# LevelShift.net
KiCad netlist of a schematic drawn in Altium Designer
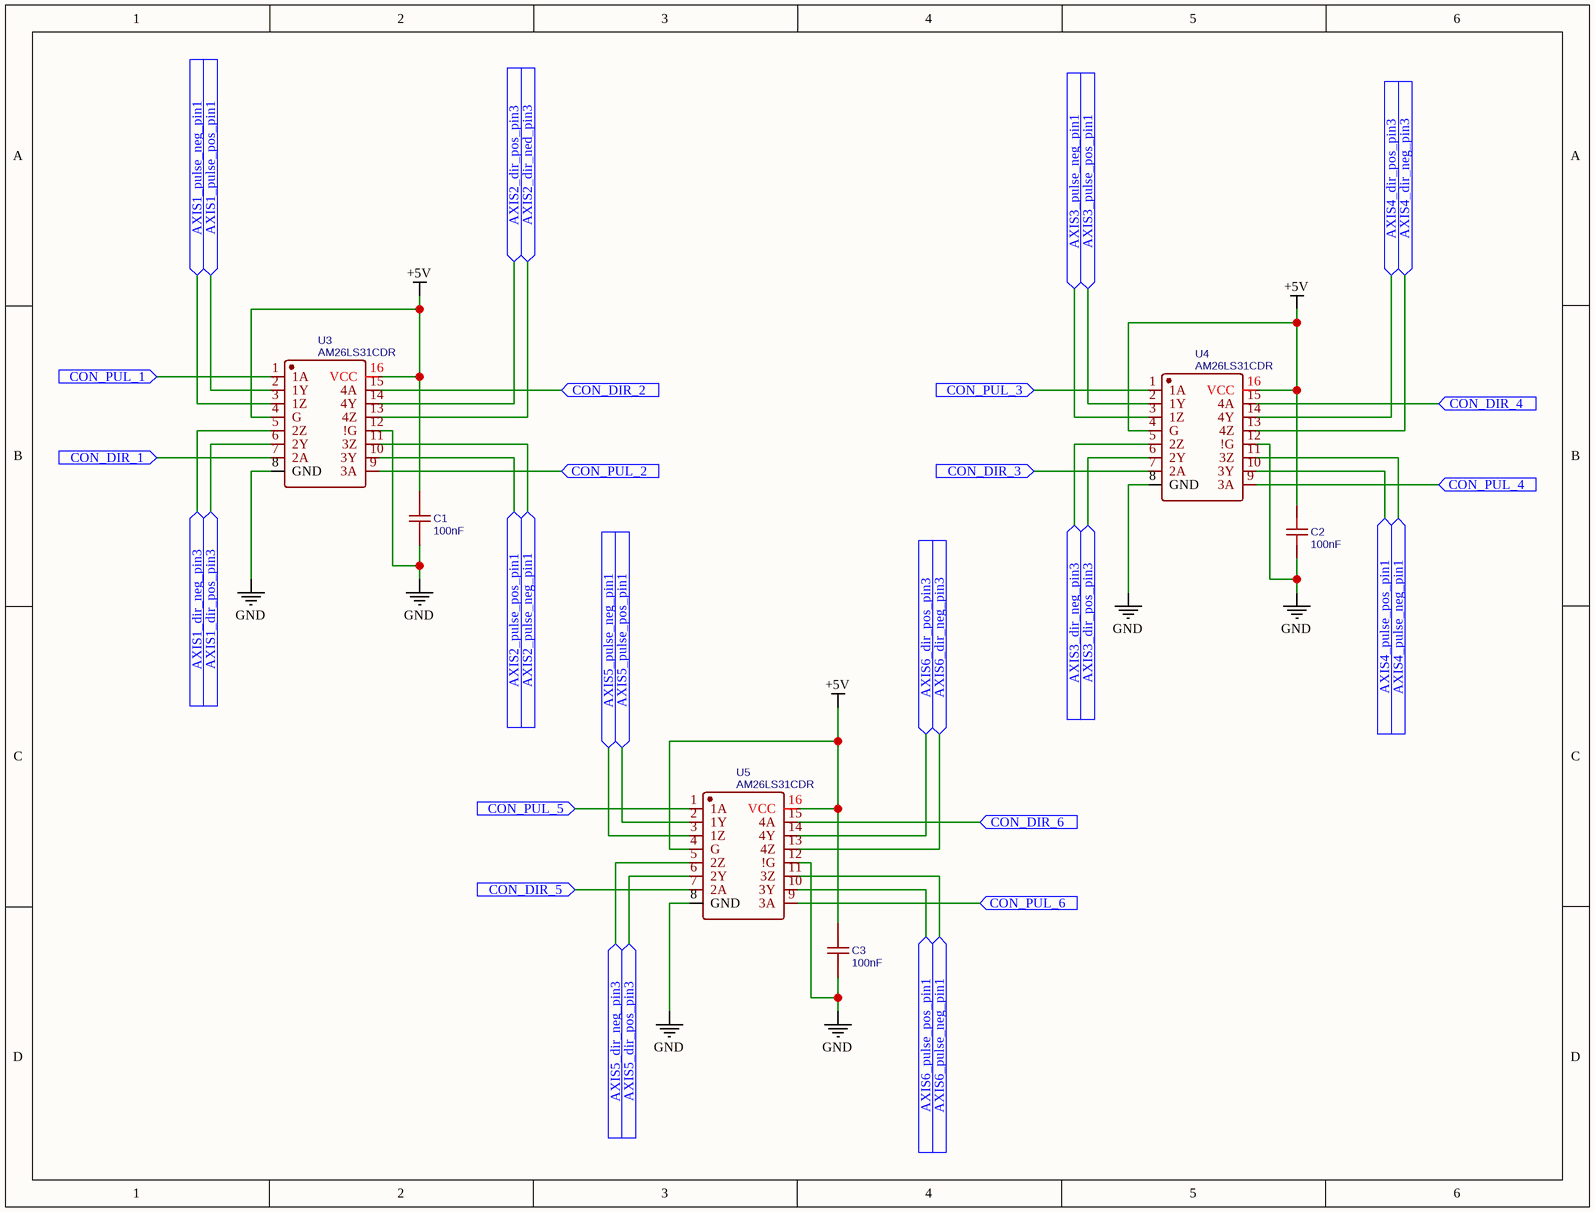
[diagram p0: LevelShift.schdoc]

(export (version "E")
  (design (tool "Eeschema 10.0.6"))
  (components
    (comp (ref "C1")
      (value "100nF")
      (fields
        (field (name "MANUFACTURER") "YAGEO")
        (field (name "MANUFACTURER PART") "CC0805KRX7R8BB104")
        (field (name "CONTRIBUTOR") "LCSC")
      )
      (libsource (lib "altium-import") (part "root_3_100nF_"))
    )
    (comp (ref "C2")
      (value "100nF")
      (fields
        (field (name "MANUFACTURER") "YAGEO")
        (field (name "MANUFACTURER PART") "CC0805KRX7R8BB104")
        (field (name "CONTRIBUTOR") "LCSC")
      )
      (libsource (lib "altium-import") (part "root_3_100nF_"))
    )
    (comp (ref "C3")
      (value "100nF")
      (fields
        (field (name "MANUFACTURER") "YAGEO")
        (field (name "MANUFACTURER PART") "CC0805KRX7R8BB104")
        (field (name "CONTRIBUTOR") "LCSC")
      )
      (libsource (lib "altium-import") (part "root_3_100nF_"))
    )
    (comp (ref "U3")
      (value "AM26LS31CDR")
      (fields (field (name "MANUFACTURER") "TI(德州仪器)"))
      (libsource (lib "altium-import") (part "root_0_AM26LS31CDR_"))
    )
    (comp (ref "U4")
      (value "AM26LS31CDR")
      (fields (field (name "MANUFACTURER") "TI(德州仪器)"))
      (libsource (lib "altium-import") (part "root_0_AM26LS31CDR_"))
    )
    (comp (ref "U5")
      (value "AM26LS31CDR")
      (fields (field (name "MANUFACTURER") "TI(德州仪器)"))
      (libsource (lib "altium-import") (part "root_0_AM26LS31CDR_"))
    )
  )
  (nets
    (net (code "1") (name "+5V") (class "Default")
      (node (ref "C1") (pin "1") (pinfunction "1_1") (pintype "passive"))
      (node (ref "C2") (pin "1") (pinfunction "1_1") (pintype "passive"))
      (node (ref "C3") (pin "1") (pinfunction "1_1") (pintype "passive"))
      (node (ref "U3") (pin "16") (pinfunction "VCC_16") (pintype "passive"))
      (node (ref "U3") (pin "4") (pinfunction "G_4") (pintype "passive"))
      (node (ref "U4") (pin "16") (pinfunction "VCC_16") (pintype "passive"))
      (node (ref "U4") (pin "4") (pinfunction "G_4") (pintype "passive"))
      (node (ref "U5") (pin "16") (pinfunction "VCC_16") (pintype "passive"))
      (node (ref "U5") (pin "4") (pinfunction "G_4") (pintype "passive"))
    )
    (net (code "2") (name "/AXIS1_dir_neg_pin3") (class "Default")
      (node (ref "U3") (pin "5") (pinfunction "2Z_5") (pintype "passive"))
    )
    (net (code "3") (name "/AXIS1_dir_pos_pin3") (class "Default")
      (node (ref "U3") (pin "6") (pinfunction "2Y_6") (pintype "passive"))
    )
    (net (code "4") (name "/AXIS1_pulse_neg_pin1") (class "Default")
      (node (ref "U3") (pin "3") (pinfunction "1Z_3") (pintype "passive"))
    )
    (net (code "5") (name "/AXIS1_pulse_pos_pin1") (class "Default")
      (node (ref "U3") (pin "2") (pinfunction "1Y_2") (pintype "passive"))
    )
    (net (code "6") (name "/AXIS2_dir_ned_pin3") (class "Default")
      (node (ref "U3") (pin "13") (pinfunction "4Z_13") (pintype "passive"))
    )
    (net (code "7") (name "/AXIS2_dir_pos_pin3") (class "Default")
      (node (ref "U3") (pin "14") (pinfunction "4Y_14") (pintype "passive"))
    )
    (net (code "8") (name "/AXIS2_pulse_neg_pin1") (class "Default")
      (node (ref "U3") (pin "11") (pinfunction "3Z_11") (pintype "passive"))
    )
    (net (code "9") (name "/AXIS2_pulse_pos_pin1") (class "Default")
      (node (ref "U3") (pin "10") (pinfunction "3Y_10") (pintype "passive"))
    )
    (net (code "10") (name "/AXIS3_dir_neg_pin3") (class "Default")
      (node (ref "U4") (pin "5") (pinfunction "2Z_5") (pintype "passive"))
    )
    (net (code "11") (name "/AXIS3_dir_pos_pin3") (class "Default")
      (node (ref "U4") (pin "6") (pinfunction "2Y_6") (pintype "passive"))
    )
    (net (code "12") (name "/AXIS3_pulse_neg_pin1") (class "Default")
      (node (ref "U4") (pin "3") (pinfunction "1Z_3") (pintype "passive"))
    )
    (net (code "13") (name "/AXIS3_pulse_pos_pin1") (class "Default")
      (node (ref "U4") (pin "2") (pinfunction "1Y_2") (pintype "passive"))
    )
    (net (code "14") (name "/AXIS4_dir_neg_pin3") (class "Default")
      (node (ref "U4") (pin "13") (pinfunction "4Z_13") (pintype "passive"))
    )
    (net (code "15") (name "/AXIS4_dir_pos_pin3") (class "Default")
      (node (ref "U4") (pin "14") (pinfunction "4Y_14") (pintype "passive"))
    )
    (net (code "16") (name "/AXIS4_pulse_neg_pin1") (class "Default")
      (node (ref "U4") (pin "11") (pinfunction "3Z_11") (pintype "passive"))
    )
    (net (code "17") (name "/AXIS4_pulse_pos_pin1") (class "Default")
      (node (ref "U4") (pin "10") (pinfunction "3Y_10") (pintype "passive"))
    )
    (net (code "18") (name "/AXIS5_dir_neg_pin3") (class "Default")
      (node (ref "U5") (pin "5") (pinfunction "2Z_5") (pintype "passive"))
    )
    (net (code "19") (name "/AXIS5_dir_pos_pin3") (class "Default")
      (node (ref "U5") (pin "6") (pinfunction "2Y_6") (pintype "passive"))
    )
    (net (code "20") (name "/AXIS5_pulse_neg_pin1") (class "Default")
      (node (ref "U5") (pin "3") (pinfunction "1Z_3") (pintype "passive"))
    )
    (net (code "21") (name "/AXIS5_pulse_pos_pin1") (class "Default")
      (node (ref "U5") (pin "2") (pinfunction "1Y_2") (pintype "passive"))
    )
    (net (code "22") (name "/AXIS6_dir_neg_pin3") (class "Default")
      (node (ref "U5") (pin "13") (pinfunction "4Z_13") (pintype "passive"))
    )
    (net (code "23") (name "/AXIS6_dir_pos_pin3") (class "Default")
      (node (ref "U5") (pin "14") (pinfunction "4Y_14") (pintype "passive"))
    )
    (net (code "24") (name "/AXIS6_pulse_neg_pin1") (class "Default")
      (node (ref "U5") (pin "11") (pinfunction "3Z_11") (pintype "passive"))
    )
    (net (code "25") (name "/AXIS6_pulse_pos_pin1") (class "Default")
      (node (ref "U5") (pin "10") (pinfunction "3Y_10") (pintype "passive"))
    )
    (net (code "26") (name "/CON_DIR_1") (class "Default")
      (node (ref "U3") (pin "7") (pinfunction "2A_7") (pintype "passive"))
    )
    (net (code "27") (name "/CON_DIR_2") (class "Default")
      (node (ref "U3") (pin "15") (pinfunction "4A_15") (pintype "passive"))
    )
    (net (code "28") (name "/CON_DIR_3") (class "Default")
      (node (ref "U4") (pin "7") (pinfunction "2A_7") (pintype "passive"))
    )
    (net (code "29") (name "/CON_DIR_4") (class "Default")
      (node (ref "U4") (pin "15") (pinfunction "4A_15") (pintype "passive"))
    )
    (net (code "30") (name "/CON_DIR_5") (class "Default")
      (node (ref "U5") (pin "7") (pinfunction "2A_7") (pintype "passive"))
    )
    (net (code "31") (name "/CON_DIR_6") (class "Default")
      (node (ref "U5") (pin "15") (pinfunction "4A_15") (pintype "passive"))
    )
    (net (code "32") (name "/CON_PUL_1") (class "Default")
      (node (ref "U3") (pin "1") (pinfunction "1A_1") (pintype "passive"))
    )
    (net (code "33") (name "/CON_PUL_2") (class "Default")
      (node (ref "U3") (pin "9") (pinfunction "3A_9") (pintype "passive"))
    )
    (net (code "34") (name "/CON_PUL_3") (class "Default")
      (node (ref "U4") (pin "1") (pinfunction "1A_1") (pintype "passive"))
    )
    (net (code "35") (name "/CON_PUL_4") (class "Default")
      (node (ref "U4") (pin "9") (pinfunction "3A_9") (pintype "passive"))
    )
    (net (code "36") (name "/CON_PUL_5") (class "Default")
      (node (ref "U5") (pin "1") (pinfunction "1A_1") (pintype "passive"))
    )
    (net (code "37") (name "/CON_PUL_6") (class "Default")
      (node (ref "U5") (pin "9") (pinfunction "3A_9") (pintype "passive"))
    )
    (net (code "38") (name "GND") (class "Default")
      (node (ref "C1") (pin "2") (pinfunction "2_2") (pintype "passive"))
      (node (ref "C2") (pin "2") (pinfunction "2_2") (pintype "passive"))
      (node (ref "C3") (pin "2") (pinfunction "2_2") (pintype "passive"))
      (node (ref "U3") (pin "12") (pinfunction "!G_12") (pintype "passive"))
      (node (ref "U3") (pin "8") (pinfunction "GND_8") (pintype "passive"))
      (node (ref "U4") (pin "12") (pinfunction "!G_12") (pintype "passive"))
      (node (ref "U4") (pin "8") (pinfunction "GND_8") (pintype "passive"))
      (node (ref "U5") (pin "12") (pinfunction "!G_12") (pintype "passive"))
      (node (ref "U5") (pin "8") (pinfunction "GND_8") (pintype "passive"))
    )
  )
)
